# corialis_breakout.net
KiCad netlist of a schematic drawn in EasyEDA Pro
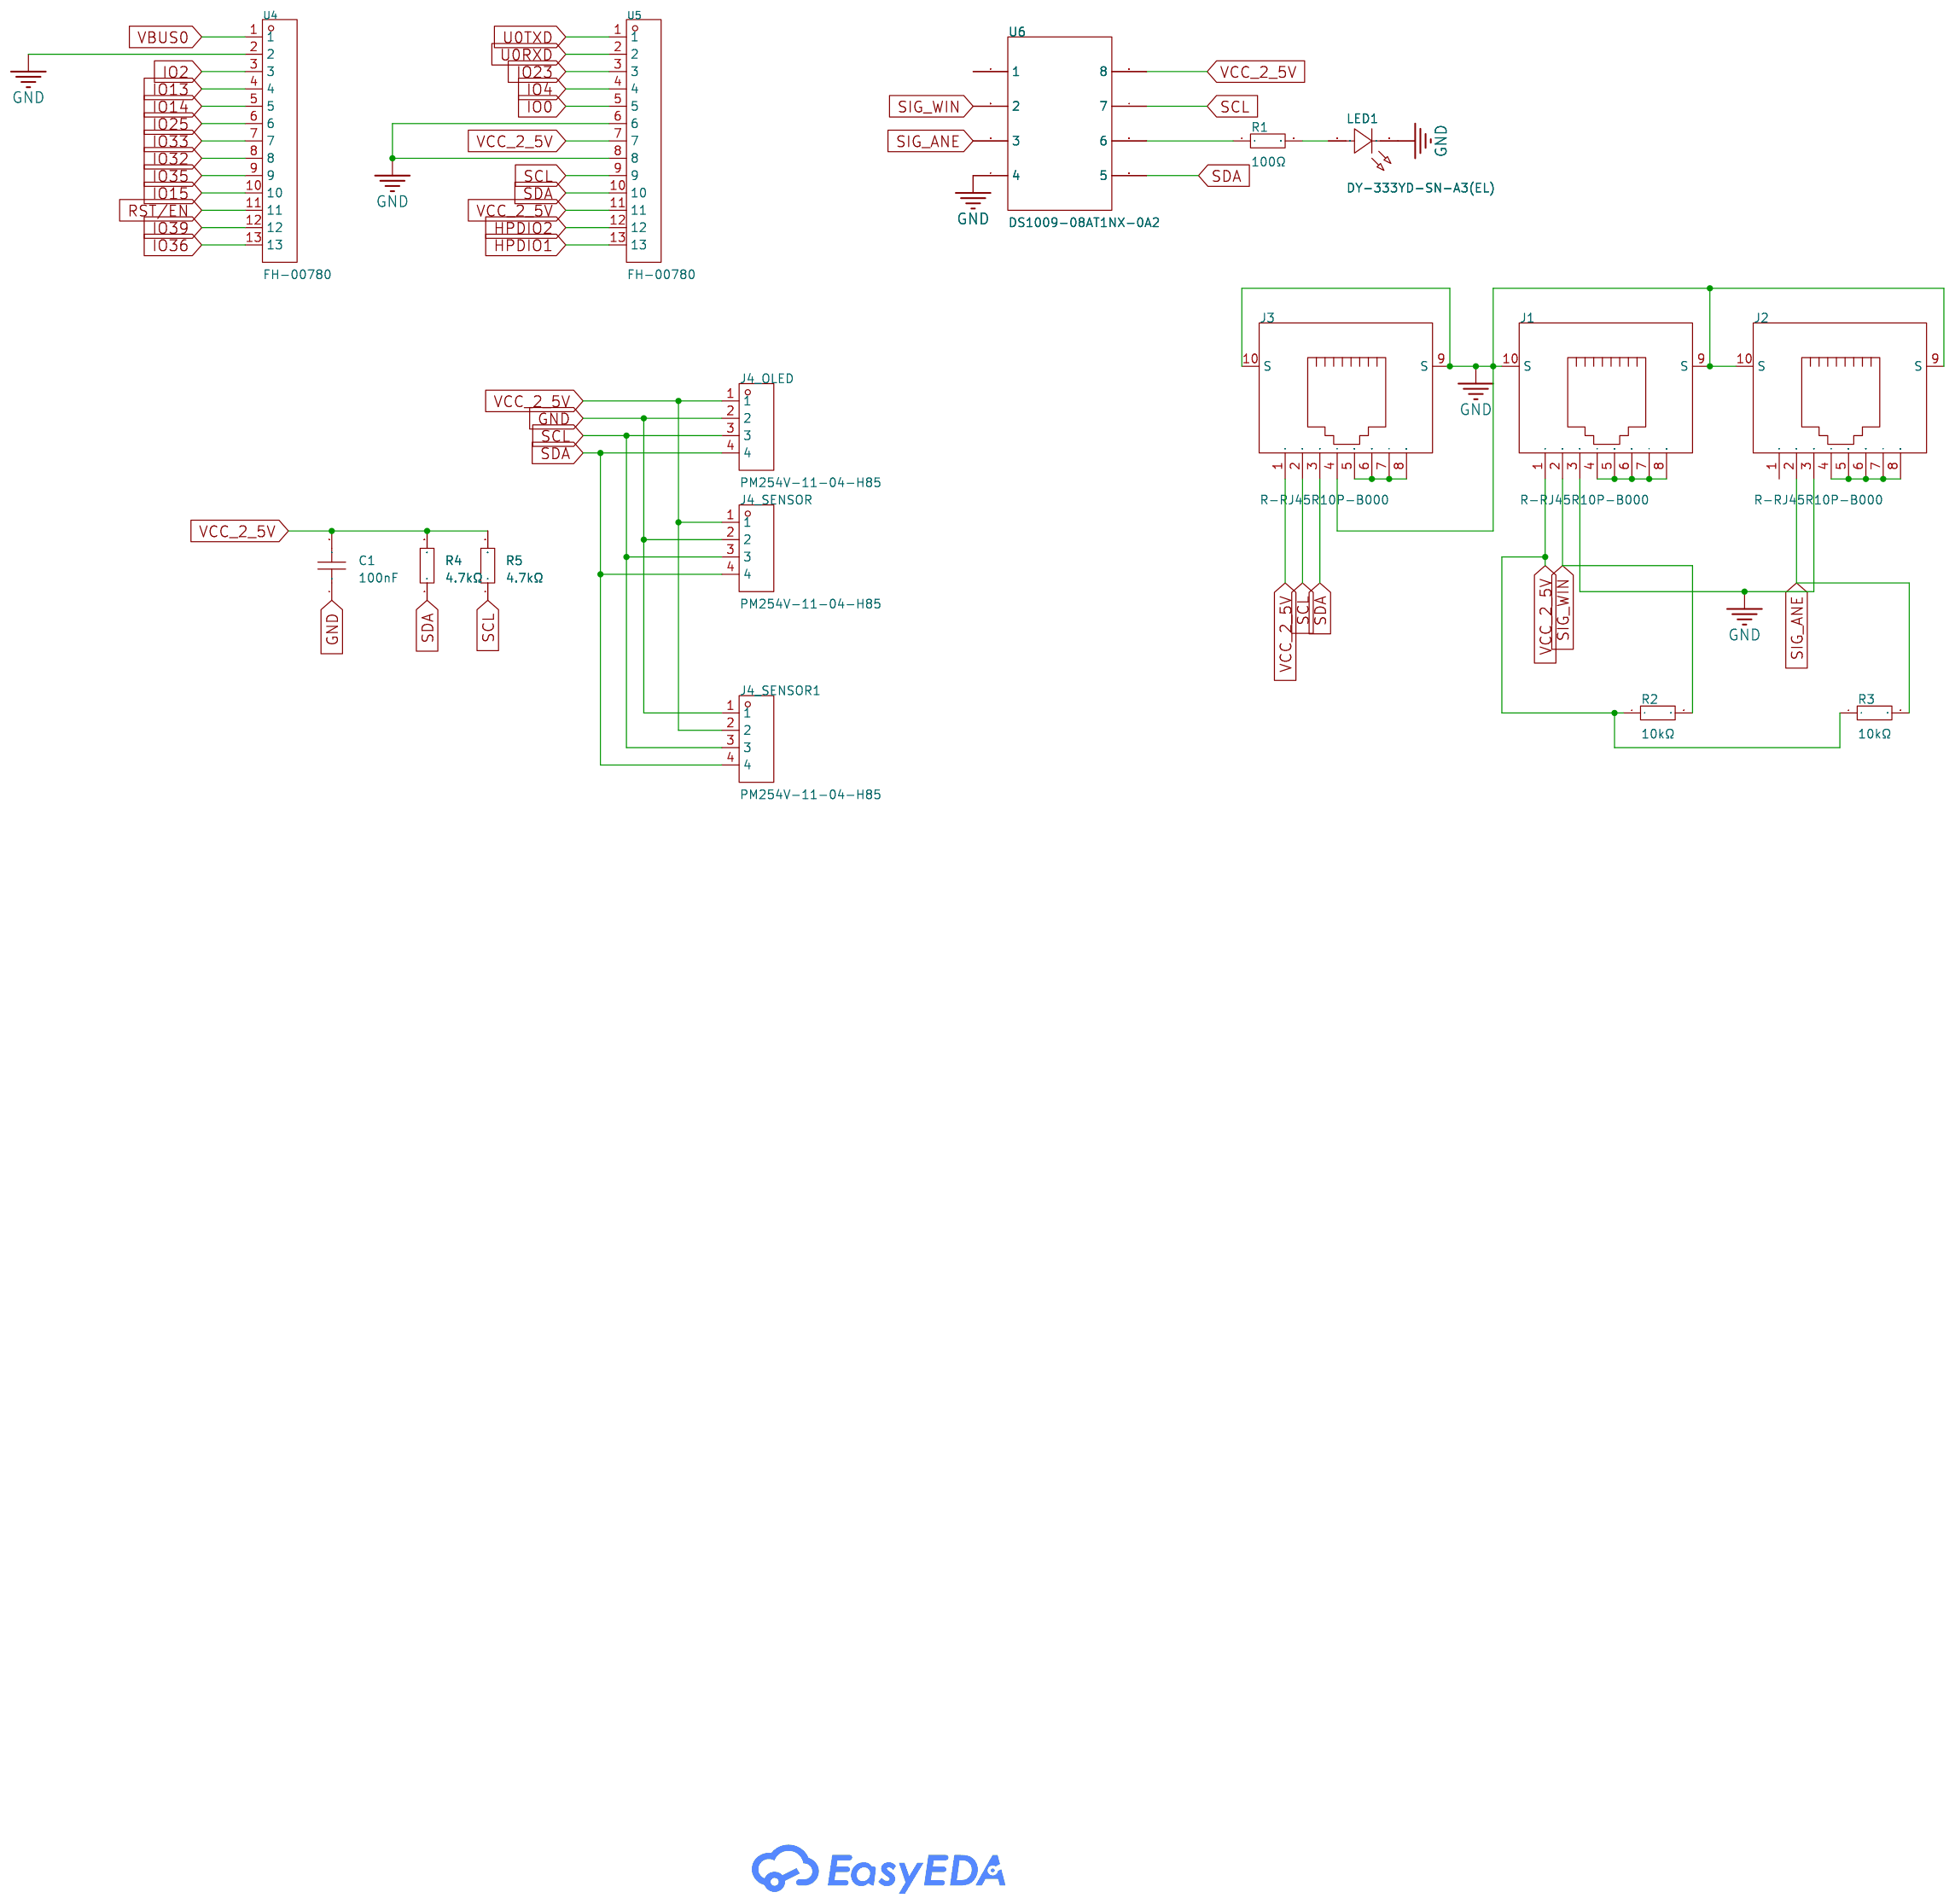
[diagram p0: schematic sheet]

(export (version "E")
  (design (tool "Eeschema 10.0.6"))
  (components
    (comp (ref "C1")
      (value "100nF")
      (footprint "easyedapro:CAP-TH_L5.8-W2.4-P2.54-D0.6")
      (fields
        (field (name "Manufacturer Part") "CC1H104ZA1ED3F5P1100")
        (field (name "Manufacturer") "Dersonic(德尔创)")
      )
      (libsource (lib "easyedapro") (part "CC1H104ZA1ED3F5P1100"))
    )
    (comp (ref "J1")
      (value "R-RJ45R10P-B000")
      (footprint "easyedapro:RJ45-TH_R-RJ45R10P-B000")
      (fields (field (name "Manufacturer") "Ckmtw(灿科盟)"))
      (libsource (lib "easyedapro") (part "R-RJ45R10P-B000"))
    )
    (comp (ref "J2")
      (value "R-RJ45R10P-B000")
      (footprint "easyedapro:RJ45-TH_R-RJ45R10P-B000")
      (fields (field (name "Manufacturer") "Ckmtw(灿科盟)"))
      (libsource (lib "easyedapro") (part "R-RJ45R10P-B000"))
    )
    (comp (ref "J3")
      (value "R-RJ45R10P-B000")
      (footprint "easyedapro:RJ45-TH_R-RJ45R10P-B000")
      (fields (field (name "Manufacturer") "Ckmtw(灿科盟)"))
      (libsource (lib "easyedapro") (part "R-RJ45R10P-B000"))
    )
    (comp (ref "J4_OLED")
      (value "PM254V-11-04-H85")
      (footprint "easyedapro:HDR-TH_4P-P2.54-V-F")
      (fields (field (name "Manufacturer") "XFCN(兴飞)"))
      (libsource (lib "easyedapro") (part "PM254V-11-04-H85"))
    )
    (comp (ref "J4_SENSOR")
      (value "PM254V-11-04-H85")
      (footprint "easyedapro:HDR-TH_4P-P2.54-V-F")
      (fields (field (name "Manufacturer") "XFCN(兴飞)"))
      (libsource (lib "easyedapro") (part "PM254V-11-04-H85"))
    )
    (comp (ref "J4_SENSOR1")
      (value "PM254V-11-04-H85")
      (footprint "easyedapro:HDR-TH_4P-P2.54-V-F")
      (fields (field (name "Manufacturer") "XFCN(兴飞)"))
      (libsource (lib "easyedapro") (part "PM254V-11-04-H85"))
    )
    (comp (ref "LED1")
      (value "DY-333YD-SN-A3(EL)")
      (fields (field (name "Manufacturer") "TONYU(东裕)"))
      (libsource (lib "easyedapro") (part "XL-1608SURC-06"))
    )
    (comp (ref "R1")
      (value "100Ω")
      (fields (field (name "Manufacturer Part") "MFR50SJT-52-100R") (field (name "Manufacturer") "YAGEO(国巨)"))
      (libsource (lib "easyedapro") (part "Res"))
    )
    (comp (ref "R2")
      (value "10kΩ")
      (footprint "easyedapro:RES-TH_BD2.4-L6.3-P10.30-D0.6")
      (fields (field (name "Manufacturer Part") "MFR50SJT-52-10K") (field (name "Manufacturer") "YAGEO(国巨)"))
      (libsource (lib "easyedapro") (part "MFR50SJT-52-10K"))
    )
    (comp (ref "R3")
      (value "10kΩ")
      (footprint "easyedapro:RES-TH_BD2.4-L6.3-P10.30-D0.6")
      (fields (field (name "Manufacturer Part") "MFR50SJT-52-10K") (field (name "Manufacturer") "YAGEO(国巨)"))
      (libsource (lib "easyedapro") (part "MFR50SJT-52-10K"))
    )
    (comp (ref "R4")
      (value "4.7kΩ")
      (footprint "easyedapro:RES-TH_BD2.2-L6.5-P10.50-D0.6")
      (fields (field (name "Manufacturer Part") "MFR50SJT-52-4K7") (field (name "Manufacturer") "YAGEO(国巨)"))
      (libsource (lib "easyedapro") (part "MFR50SJT-52-4K7"))
    )
    (comp (ref "R5")
      (value "4.7kΩ")
      (footprint "easyedapro:RES-TH_BD2.2-L6.5-P10.50-D0.6")
      (fields (field (name "Manufacturer Part") "MFR50SJT-52-4K7") (field (name "Manufacturer") "YAGEO(国巨)"))
      (libsource (lib "easyedapro") (part "MFR50SJT-52-4K7"))
    )
    (comp (ref "U4")
      (value "FH-00780")
      (footprint "easyedapro:HDR-TH_13P-P2.54-V-F")
      (fields (field (name "Manufacturer") "Liansheng(连盛)"))
      (libsource (lib "easyedapro") (part "FH-00780"))
    )
    (comp (ref "U5")
      (value "FH-00780")
      (footprint "easyedapro:HDR-TH_13P-P2.54-V-F")
      (fields (field (name "Manufacturer") "Liansheng(连盛)"))
      (libsource (lib "easyedapro") (part "FH-00780"))
    )
    (comp (ref "U6")
      (value "DS1009-08AT1NX-0A2")
      (footprint "easyedapro:DIP-8_L10.2-W10.2-P2.54-LS7.6-BL")
      (fields (field (name "Manufacturer") "CONNFLY"))
      (libsource (lib "easyedapro") (part "DS1009-08AT1NX-0A2"))
    )
  )
  (nets
    (net (code "1") (name "GND") (class "Default")
      (node (ref "C1") (pin "1") (pinfunction "1_1") (pintype "unspecified"))
      (node (ref "J1") (pin "10") (pinfunction "S_10") (pintype "unspecified"))
      (node (ref "J1") (pin "3") (pinfunction "3_3") (pintype "unspecified"))
      (node (ref "J1") (pin "9") (pinfunction "S_9") (pintype "unspecified"))
      (node (ref "J2") (pin "10") (pinfunction "S_10") (pintype "unspecified"))
      (node (ref "J2") (pin "3") (pinfunction "3_3") (pintype "unspecified"))
      (node (ref "J2") (pin "9") (pinfunction "S_9") (pintype "unspecified"))
      (node (ref "J3") (pin "10") (pinfunction "S_10") (pintype "unspecified"))
      (node (ref "J3") (pin "4") (pinfunction "4_4") (pintype "unspecified"))
      (node (ref "J3") (pin "9") (pinfunction "S_9") (pintype "unspecified"))
      (node (ref "J4_OLED") (pin "2") (pinfunction "2_2") (pintype "unspecified"))
      (node (ref "J4_SENSOR") (pin "2") (pinfunction "2_2") (pintype "unspecified"))
      (node (ref "J4_SENSOR1") (pin "1") (pinfunction "1_1") (pintype "unspecified"))
      (node (ref "LED1") (pin "1") (pinfunction "K_1") (pintype "unspecified"))
      (node (ref "U4") (pin "2") (pinfunction "2_2") (pintype "input"))
      (node (ref "U5") (pin "6") (pinfunction "6_6") (pintype "input"))
      (node (ref "U5") (pin "8") (pinfunction "8_8") (pintype "input"))
      (node (ref "U6") (pin "4") (pinfunction "4_4") (pintype "input"))
    )
    (net (code "2") (name "HPDIO1") (class "Default")
      (node (ref "U5") (pin "13") (pinfunction "13_13") (pintype "input"))
    )
    (net (code "3") (name "HPDIO2") (class "Default")
      (node (ref "U5") (pin "12") (pinfunction "12_12") (pintype "input"))
    )
    (net (code "4") (name "IO0") (class "Default")
      (node (ref "U5") (pin "5") (pinfunction "5_5") (pintype "input"))
    )
    (net (code "5") (name "IO2") (class "Default")
      (node (ref "U4") (pin "3") (pinfunction "3_3") (pintype "input"))
    )
    (net (code "6") (name "IO4") (class "Default")
      (node (ref "U5") (pin "4") (pinfunction "4_4") (pintype "input"))
    )
    (net (code "7") (name "IO13") (class "Default")
      (node (ref "U4") (pin "4") (pinfunction "4_4") (pintype "input"))
    )
    (net (code "8") (name "IO14") (class "Default")
      (node (ref "U4") (pin "5") (pinfunction "5_5") (pintype "input"))
    )
    (net (code "9") (name "IO15") (class "Default")
      (node (ref "U4") (pin "10") (pinfunction "10_10") (pintype "input"))
    )
    (net (code "10") (name "IO23") (class "Default")
      (node (ref "U5") (pin "3") (pinfunction "3_3") (pintype "input"))
    )
    (net (code "11") (name "IO25") (class "Default")
      (node (ref "U4") (pin "6") (pinfunction "6_6") (pintype "input"))
    )
    (net (code "12") (name "IO32") (class "Default")
      (node (ref "U4") (pin "8") (pinfunction "8_8") (pintype "input"))
    )
    (net (code "13") (name "IO33") (class "Default")
      (node (ref "U4") (pin "7") (pinfunction "7_7") (pintype "input"))
    )
    (net (code "14") (name "IO35") (class "Default")
      (node (ref "U4") (pin "9") (pinfunction "9_9") (pintype "input"))
    )
    (net (code "15") (name "IO36") (class "Default")
      (node (ref "U4") (pin "13") (pinfunction "13_13") (pintype "input"))
    )
    (net (code "16") (name "IO39") (class "Default")
      (node (ref "U4") (pin "12") (pinfunction "12_12") (pintype "input"))
    )
    (net (code "17") (name "Net-(J1-Pad4)") (class "Default")
      (node (ref "J1") (pin "4") (pinfunction "4_4") (pintype "unspecified"))
      (node (ref "J1") (pin "5") (pinfunction "5_5") (pintype "unspecified"))
      (node (ref "J1") (pin "6") (pinfunction "6_6") (pintype "unspecified"))
      (node (ref "J1") (pin "7") (pinfunction "7_7") (pintype "unspecified"))
      (node (ref "J1") (pin "8") (pinfunction "8_8") (pintype "unspecified"))
    )
    (net (code "18") (name "Net-(J2-Pad4)") (class "Default")
      (node (ref "J2") (pin "4") (pinfunction "4_4") (pintype "unspecified"))
      (node (ref "J2") (pin "5") (pinfunction "5_5") (pintype "unspecified"))
      (node (ref "J2") (pin "6") (pinfunction "6_6") (pintype "unspecified"))
      (node (ref "J2") (pin "7") (pinfunction "7_7") (pintype "unspecified"))
      (node (ref "J2") (pin "8") (pinfunction "8_8") (pintype "unspecified"))
    )
    (net (code "19") (name "Net-(J3-Pad5)") (class "Default")
      (node (ref "J3") (pin "5") (pinfunction "5_5") (pintype "unspecified"))
      (node (ref "J3") (pin "6") (pinfunction "6_6") (pintype "unspecified"))
      (node (ref "J3") (pin "7") (pinfunction "7_7") (pintype "unspecified"))
      (node (ref "J3") (pin "8") (pinfunction "8_8") (pintype "unspecified"))
    )
    (net (code "20") (name "Net-(LED1-A)") (class "Default")
      (node (ref "LED1") (pin "2") (pinfunction "A_2") (pintype "unspecified"))
      (node (ref "R1") (pin "2") (pinfunction "2_2") (pintype "input"))
    )
    (net (code "21") (name "Net-(R1-Pad1)") (class "Default")
      (node (ref "R1") (pin "1") (pinfunction "1_1") (pintype "input"))
      (node (ref "U6") (pin "6") (pinfunction "6_6") (pintype "input"))
    )
    (net (code "22") (name "RST{slash}EN") (class "Default")
      (node (ref "U4") (pin "11") (pinfunction "11_11") (pintype "input"))
    )
    (net (code "23") (name "SCL") (class "Default")
      (node (ref "J3") (pin "2") (pinfunction "2_2") (pintype "unspecified"))
      (node (ref "J4_OLED") (pin "3") (pinfunction "3_3") (pintype "unspecified"))
      (node (ref "J4_SENSOR") (pin "3") (pinfunction "3_3") (pintype "unspecified"))
      (node (ref "J4_SENSOR1") (pin "3") (pinfunction "3_3") (pintype "unspecified"))
      (node (ref "R5") (pin "1") (pinfunction "1_1") (pintype "unspecified"))
      (node (ref "U5") (pin "9") (pinfunction "9_9") (pintype "input"))
      (node (ref "U6") (pin "7") (pinfunction "7_7") (pintype "input"))
    )
    (net (code "24") (name "SDA") (class "Default")
      (node (ref "J3") (pin "3") (pinfunction "3_3") (pintype "unspecified"))
      (node (ref "J4_OLED") (pin "4") (pinfunction "4_4") (pintype "unspecified"))
      (node (ref "J4_SENSOR") (pin "4") (pinfunction "4_4") (pintype "unspecified"))
      (node (ref "J4_SENSOR1") (pin "4") (pinfunction "4_4") (pintype "unspecified"))
      (node (ref "R4") (pin "1") (pinfunction "1_1") (pintype "unspecified"))
      (node (ref "U5") (pin "10") (pinfunction "10_10") (pintype "input"))
      (node (ref "U6") (pin "5") (pinfunction "5_5") (pintype "input"))
    )
    (net (code "25") (name "SIG_ANE") (class "Default")
      (node (ref "J2") (pin "2") (pinfunction "2_2") (pintype "unspecified"))
      (node (ref "R3") (pin "2") (pinfunction "2_2") (pintype "unspecified"))
      (node (ref "U6") (pin "3") (pinfunction "3_3") (pintype "input"))
    )
    (net (code "26") (name "SIG_WIN") (class "Default")
      (node (ref "J1") (pin "2") (pinfunction "2_2") (pintype "unspecified"))
      (node (ref "R2") (pin "2") (pinfunction "2_2") (pintype "unspecified"))
      (node (ref "U6") (pin "2") (pinfunction "2_2") (pintype "input"))
    )
    (net (code "27") (name "U0RXD") (class "Default")
      (node (ref "U5") (pin "2") (pinfunction "2_2") (pintype "input"))
    )
    (net (code "28") (name "U0TXD") (class "Default")
      (node (ref "U5") (pin "1") (pinfunction "1_1") (pintype "input"))
    )
    (net (code "29") (name "VBUS0") (class "Default")
      (node (ref "U4") (pin "1") (pinfunction "1_1") (pintype "input"))
    )
    (net (code "30") (name "VCC_2_5V") (class "Default")
      (node (ref "C1") (pin "2") (pinfunction "2_2") (pintype "unspecified"))
      (node (ref "J1") (pin "1") (pinfunction "1_1") (pintype "unspecified"))
      (node (ref "J3") (pin "1") (pinfunction "1_1") (pintype "unspecified"))
      (node (ref "J4_OLED") (pin "1") (pinfunction "1_1") (pintype "unspecified"))
      (node (ref "J4_SENSOR") (pin "1") (pinfunction "1_1") (pintype "unspecified"))
      (node (ref "J4_SENSOR1") (pin "2") (pinfunction "2_2") (pintype "unspecified"))
      (node (ref "R2") (pin "1") (pinfunction "1_1") (pintype "unspecified"))
      (node (ref "R3") (pin "1") (pinfunction "1_1") (pintype "unspecified"))
      (node (ref "R4") (pin "2") (pinfunction "2_2") (pintype "unspecified"))
      (node (ref "R5") (pin "2") (pinfunction "2_2") (pintype "unspecified"))
      (node (ref "U5") (pin "11") (pinfunction "11_11") (pintype "input"))
      (node (ref "U5") (pin "7") (pinfunction "7_7") (pintype "input"))
      (node (ref "U6") (pin "8") (pinfunction "8_8") (pintype "input"))
    )
    (net (code "31") (name "unconnected-(J2-Pad1)") (class "Default")
      (node (ref "J2") (pin "1") (pinfunction "1_1") (pintype "unspecified"))
    )
    (net (code "32") (name "unconnected-(U6-Pad1)") (class "Default")
      (node (ref "U6") (pin "1") (pinfunction "1_1") (pintype "input"))
    )
  )
)
